# DCI_USB.net
KiCad netlist of a schematic drawn in Altium Designer
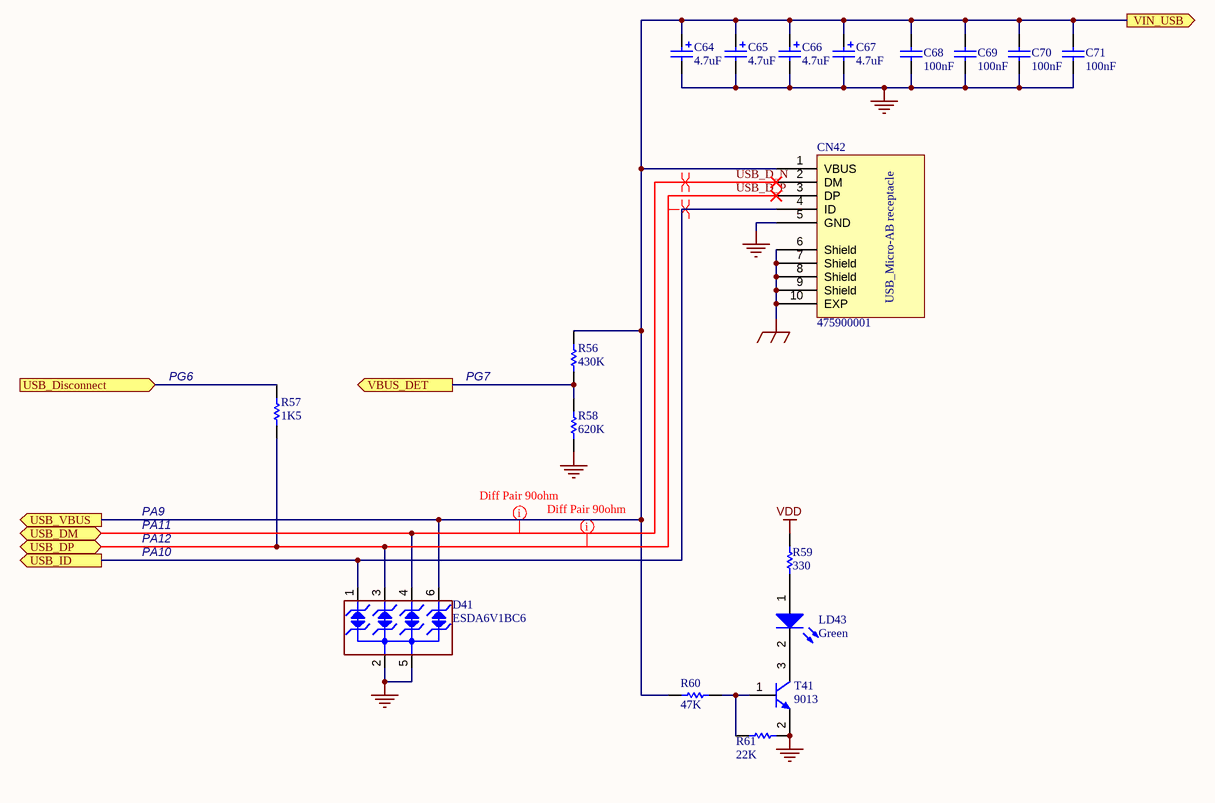
[diagram p0: DCI_USB.SchDoc]

(export (version "E")
  (design (tool "Eeschema 10.0.6"))
  (components
    (comp (ref "C64")
      (value "4.7uF")
      (footprint "TAN-A - XNo")
      (description "Polarized Capacitor (Radial)")
      (fields (field (name "PUBLISHER") "Altium Limited"))
      (libsource (lib "Miscellaneous Devices") (part "Cap Pol1"))
    )
    (comp (ref "C65")
      (value "4.7uF")
      (footprint "TAN-A - XUp")
      (description "Polarized Capacitor (Radial)")
      (fields (field (name "PUBLISHER") "Altium Limited"))
      (libsource (lib "Miscellaneous Devices") (part "Cap Pol1"))
    )
    (comp (ref "C66")
      (value "4.7uF")
      (footprint "TAN-A - XNo")
      (description "Polarized Capacitor (Radial)")
      (fields (field (name "PUBLISHER") "Altium Limited"))
      (libsource (lib "Miscellaneous Devices") (part "Cap Pol1"))
    )
    (comp (ref "C67")
      (value "4.7uF")
      (footprint "TAN-A - XDown")
      (description "Polarized Capacitor (Radial)")
      (fields (field (name "PUBLISHER") "Altium Limited"))
      (libsource (lib "Miscellaneous Devices") (part "Cap Pol1"))
    )
    (comp (ref "C68")
      (value "100nF")
      (footprint "0603C")
      (description "Capacitor")
      (fields (field (name "PUBLISHER") "Altium Limited"))
      (libsource (lib "Miscellaneous Devices") (part "Cap"))
    )
    (comp (ref "C69")
      (value "100nF")
      (footprint "0603C")
      (description "Capacitor")
      (fields (field (name "PUBLISHER") "Altium Limited"))
      (libsource (lib "Miscellaneous Devices") (part "Cap"))
    )
    (comp (ref "C70")
      (value "100nF")
      (footprint "0603C")
      (description "Capacitor")
      (fields (field (name "PUBLISHER") "Altium Limited"))
      (libsource (lib "Miscellaneous Devices") (part "Cap"))
    )
    (comp (ref "C71")
      (value "100nF")
      (footprint "0603C")
      (description "Capacitor")
      (fields (field (name "PUBLISHER") "Altium Limited"))
      (libsource (lib "Miscellaneous Devices") (part "Cap"))
    )
    (comp (ref "CN42")
      (value "475900001")
      (footprint "MOLEX_47590001")
      (libsource (lib "mb1045") (part "475900001"))
    )
    (comp (ref "D41")
      (value "ESDA6V1BC6")
      (footprint "SOT23-6L")
      (description "4-line ESD protection")
      (libsource (lib "DCI_MB1137") (part "ESDA6V1BC6"))
    )
    (comp (ref "LD43")
      (value "Green")
      (footprint "0603D-G")
      (description "Typical RED, GREEN, YELLOW, AMBER GaAs LED")
      (fields (field (name "PUBLISHER") "Altium Limited"))
      (libsource (lib "Miscellaneous Devices") (part "LED2"))
    )
    (comp (ref "R56")
      (value "430K")
      (footprint "0603R")
      (description "Resistor")
      (fields (field (name "PUBLISHER") "Altium Limited"))
      (libsource (lib "Miscellaneous Devices") (part "res1"))
    )
    (comp (ref "R57")
      (value "1K5")
      (footprint "0603R")
      (description "Resistor 0402 / 0603 / 0805")
      (libsource (lib "Miscellaneous Devices") (part "Res1"))
    )
    (comp (ref "R58")
      (value "620K")
      (footprint "0603R")
      (description "Resistor")
      (fields (field (name "PUBLISHER") "Altium Limited"))
      (libsource (lib "Miscellaneous Devices") (part "res1"))
    )
    (comp (ref "R59")
      (value "330")
      (footprint "0603R")
      (description "Resistor")
      (fields (field (name "PUBLISHER") "Altium Limited"))
      (libsource (lib "Miscellaneous Devices") (part "res1"))
    )
    (comp (ref "R60")
      (value "47K")
      (footprint "0603R")
      (description "Resistor")
      (fields (field (name "PUBLISHER") "Altium Limited"))
      (libsource (lib "Miscellaneous Devices") (part "res1"))
    )
    (comp (ref "R61")
      (value "22K")
      (footprint "0603R")
      (description "Resistor")
      (fields (field (name "PUBLISHER") "Altium Limited"))
      (libsource (lib "Miscellaneous Devices") (part "res1"))
    )
    (comp (ref "T41")
      (value "9013")
      (footprint "SOT-23")
      (description "NPN Bipolar Transistor")
      (fields (field (name "PUBLISHER") "Altium Limited"))
      (libsource (lib "MB1167") (part "NPN"))
    )
  )
  (nets
    (net (code "1") (name "/USB_D_N") (class "Default")
      (node (ref "CN42") (pin "2") (pinfunction "DM_2") (pintype "passive"))
      (node (ref "D41") (pin "4") (pinfunction "IO3_4") (pintype "passive"))
    )
    (net (code "2") (name "/USB_D_P") (class "Default")
      (node (ref "CN42") (pin "3") (pinfunction "DP_3") (pintype "passive"))
      (node (ref "D41") (pin "3") (pinfunction "GND_3") (pintype "passive"))
      (node (ref "R57") (pin "1") (pinfunction "1_1") (pintype "passive"))
    )
    (net (code "3") (name "/USB_Disconnect") (class "Default")
      (node (ref "R57") (pin "2") (pinfunction "2_2") (pintype "passive"))
    )
    (net (code "4") (name "/USB_ID") (class "Default")
      (node (ref "CN42") (pin "4") (pinfunction "ID_4") (pintype "passive"))
      (node (ref "D41") (pin "1") (pinfunction "IO1_1") (pintype "passive"))
    )
    (net (code "5") (name "/USB_VBUS") (class "Default")
      (node (ref "C64") (pin "1") (pinfunction "1_1") (pintype "passive"))
      (node (ref "C65") (pin "1") (pinfunction "1_1") (pintype "passive"))
      (node (ref "C66") (pin "1") (pinfunction "1_1") (pintype "passive"))
      (node (ref "C67") (pin "1") (pinfunction "1_1") (pintype "passive"))
      (node (ref "C68") (pin "1") (pinfunction "1_1") (pintype "passive"))
      (node (ref "C69") (pin "1") (pinfunction "1_1") (pintype "passive"))
      (node (ref "C70") (pin "1") (pinfunction "1_1") (pintype "passive"))
      (node (ref "C71") (pin "1") (pinfunction "1_1") (pintype "passive"))
      (node (ref "CN42") (pin "1") (pinfunction "VBUS_1") (pintype "passive"))
      (node (ref "D41") (pin "6") (pinfunction "NC_6") (pintype "passive"))
      (node (ref "R56") (pin "1") (pinfunction "1_1") (pintype "passive"))
      (node (ref "R60") (pin "1") (pinfunction "1_1") (pintype "passive"))
    )
    (net (code "6") (name "/VBUS_DET") (class "Default")
      (node (ref "R56") (pin "2") (pinfunction "2_2") (pintype "passive"))
      (node (ref "R58") (pin "1") (pinfunction "1_1") (pintype "passive"))
    )
    (net (code "7") (name "EGND") (class "Default")
      (node (ref "CN42") (pin "10") (pinfunction "EXP_10") (pintype "passive"))
      (node (ref "CN42") (pin "6") (pinfunction "Shield_6") (pintype "passive"))
      (node (ref "CN42") (pin "7") (pinfunction "Shield_7") (pintype "passive"))
      (node (ref "CN42") (pin "8") (pinfunction "Shield_8") (pintype "passive"))
      (node (ref "CN42") (pin "9") (pinfunction "Shield_9") (pintype "passive"))
    )
    (net (code "8") (name "GND") (class "Default")
      (node (ref "C64") (pin "2") (pinfunction "2_2") (pintype "passive"))
      (node (ref "C65") (pin "2") (pinfunction "2_2") (pintype "passive"))
      (node (ref "C66") (pin "2") (pinfunction "2_2") (pintype "passive"))
      (node (ref "C67") (pin "2") (pinfunction "2_2") (pintype "passive"))
      (node (ref "C68") (pin "2") (pinfunction "2_2") (pintype "passive"))
      (node (ref "C69") (pin "2") (pinfunction "2_2") (pintype "passive"))
      (node (ref "C70") (pin "2") (pinfunction "2_2") (pintype "passive"))
      (node (ref "C71") (pin "2") (pinfunction "2_2") (pintype "passive"))
      (node (ref "CN42") (pin "5") (pinfunction "GND_5") (pintype "passive"))
      (node (ref "D41") (pin "2") (pinfunction "IO2_2") (pintype "passive"))
      (node (ref "D41") (pin "5") (pinfunction "IO4_5") (pintype "passive"))
      (node (ref "R58") (pin "2") (pinfunction "2_2") (pintype "passive"))
      (node (ref "R61") (pin "1") (pinfunction "1_1") (pintype "passive"))
      (node (ref "T41") (pin "2") (pinfunction "E_2") (pintype "passive"))
    )
    (net (code "9") (name "Net-(LD43-A)") (class "Default")
      (node (ref "LD43") (pin "1") (pinfunction "A_1") (pintype "passive"))
      (node (ref "R59") (pin "1") (pinfunction "1_1") (pintype "passive"))
    )
    (net (code "10") (name "Net-(LD43-K)") (class "Default")
      (node (ref "LD43") (pin "2") (pinfunction "K_2") (pintype "passive"))
      (node (ref "T41") (pin "3") (pinfunction "C_3") (pintype "passive"))
    )
    (net (code "11") (name "Net-(T41-B)") (class "Default")
      (node (ref "R60") (pin "2") (pinfunction "2_2") (pintype "passive"))
      (node (ref "R61") (pin "2") (pinfunction "2_2") (pintype "passive"))
      (node (ref "T41") (pin "1") (pinfunction "B_1") (pintype "passive"))
    )
    (net (code "12") (name "VDD") (class "Default")
      (node (ref "R59") (pin "2") (pinfunction "2_2") (pintype "passive"))
    )
  )
)
